# schematic.net
KiCad netlist of a schematic drawn in EAGLE
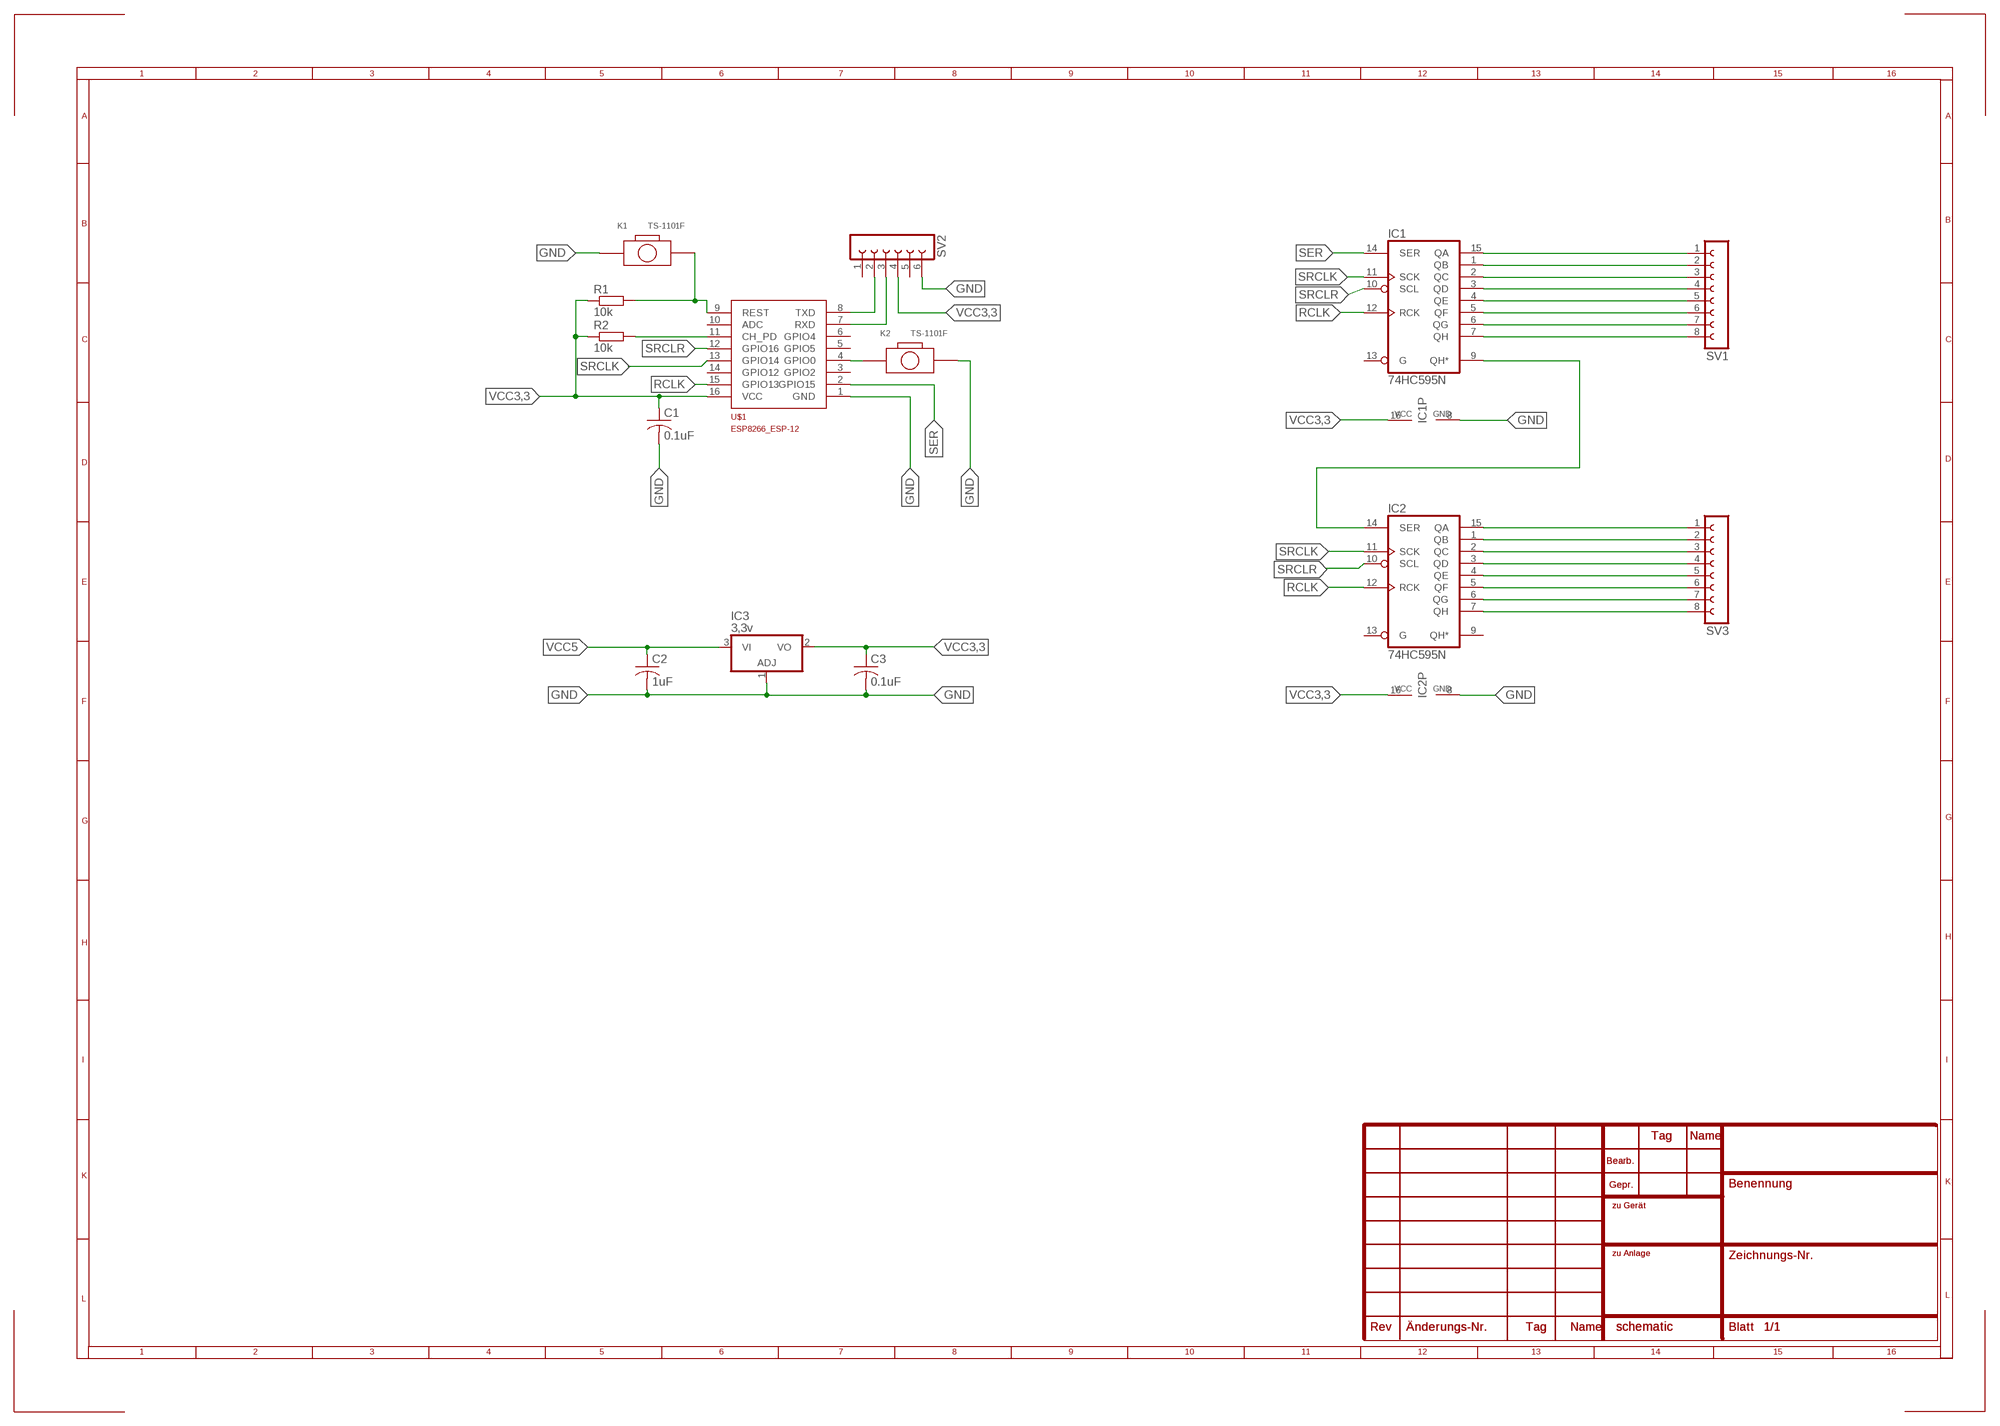
[diagram p0: schematic, sheet 1]

(export (version "E")
  (design (tool "Eeschema 10.0.6"))
  (components
    (comp (ref "C1")
      (value "0.1uF")
      (footprint "eagle-import:C1608")
      (libsource (lib "eagle-import") (part "C-USC1608"))
    )
    (comp (ref "C2")
      (value "1uF")
      (footprint "eagle-import:C1608")
      (libsource (lib "eagle-import") (part "C-USC1608"))
    )
    (comp (ref "C3")
      (value "0.1uF")
      (footprint "eagle-import:C1608")
      (libsource (lib "eagle-import") (part "C-USC1608"))
    )
    (comp (ref "IC1")
      (value "74HC595N")
      (footprint "eagle-import:DIL16")
      (libsource (lib "eagle-import") (part "74595NHC"))
    )
    (comp (ref "IC2")
      (value "74HC595N")
      (footprint "eagle-import:DIL16")
      (libsource (lib "eagle-import") (part "74595NHC"))
    )
    (comp (ref "IC3")
      (value "3,3v")
      (footprint "eagle-import:TO220H")
      (libsource (lib "eagle-import") (part "317T"))
    )
    (comp (ref "K1")
      (value "TS-1101F")
      (footprint "eagle-import:SW2-3.4X6.0X3.55MM-90D")
      (libsource (lib "eagle-import") (part "DIP-BUTTON-FRONT-WHITE(2P-3.4X6MM)"))
    )
    (comp (ref "K2")
      (value "TS-1101F")
      (footprint "eagle-import:SW2-3.4X6.0X3.55MM-90D")
      (libsource (lib "eagle-import") (part "DIP-BUTTON-FRONT-WHITE(2P-3.4X6MM)"))
    )
    (comp (ref "R1")
      (value "10k")
      (footprint "eagle-import:R0805")
      (libsource (lib "eagle-import") (part "R-EU_R0805"))
    )
    (comp (ref "R2")
      (value "10k")
      (footprint "eagle-import:R0805")
      (libsource (lib "eagle-import") (part "R-EU_R0805"))
    )
    (comp (ref "SV1")
      (value "FE08-1")
      (footprint "eagle-import:FE08")
      (libsource (lib "eagle-import") (part "FE08-1"))
    )
    (comp (ref "SV2")
      (value "FE06-1")
      (footprint "eagle-import:FE06")
      (libsource (lib "eagle-import") (part "FE06-1"))
    )
    (comp (ref "SV3")
      (value "FE08-1")
      (footprint "eagle-import:FE08")
      (libsource (lib "eagle-import") (part "FE08-1"))
    )
    (comp (ref "U$1")
      (value "ESP8266_ESP-12")
      (footprint "eagle-import:ESP8266-ESP12")
      (libsource (lib "eagle-import") (part "ESP8266_ESP-12"))
    )
  )
  (nets
    (net (code "1") (name "GND") (class "Default")
      (node (ref "C1") (pin "2") (pinfunction "2_2") (pintype "passive"))
      (node (ref "C2") (pin "2") (pinfunction "2_2") (pintype "passive"))
      (node (ref "C3") (pin "2") (pinfunction "2_2") (pintype "passive"))
      (node (ref "IC1") (pin "8") (pinfunction "GND_8") (pintype "power_in"))
      (node (ref "IC2") (pin "8") (pinfunction "GND_8") (pintype "power_in"))
      (node (ref "IC3") (pin "1") (pinfunction "ADJ_1") (pintype "input"))
      (node (ref "K1") (pin "P$1") (pinfunction "1_P$1") (pintype "bidirectional"))
      (node (ref "K2") (pin "P$2") (pinfunction "2_P$2") (pintype "bidirectional"))
      (node (ref "SV2") (pin "6") (pinfunction "6_6") (pintype "passive"))
      (node (ref "U$1") (pin "1") (pinfunction "GND_1") (pintype "bidirectional"))
    )
    (net (code "2") (name "Net-(IC1A-QA)") (class "Default")
      (node (ref "IC1") (pin "15") (pinfunction "QA_15") (pintype "tri_state"))
      (node (ref "SV1") (pin "1") (pinfunction "1_1") (pintype "passive"))
    )
    (net (code "3") (name "Net-(IC1A-QB)") (class "Default")
      (node (ref "IC1") (pin "1") (pinfunction "QB_1") (pintype "tri_state"))
      (node (ref "SV1") (pin "2") (pinfunction "2_2") (pintype "passive"))
    )
    (net (code "4") (name "Net-(IC1A-QC)") (class "Default")
      (node (ref "IC1") (pin "2") (pinfunction "QC_2") (pintype "tri_state"))
      (node (ref "SV1") (pin "3") (pinfunction "3_3") (pintype "passive"))
    )
    (net (code "5") (name "Net-(IC1A-QD)") (class "Default")
      (node (ref "IC1") (pin "3") (pinfunction "QD_3") (pintype "tri_state"))
      (node (ref "SV1") (pin "4") (pinfunction "4_4") (pintype "passive"))
    )
    (net (code "6") (name "Net-(IC1A-QE)") (class "Default")
      (node (ref "IC1") (pin "4") (pinfunction "QE_4") (pintype "tri_state"))
      (node (ref "SV1") (pin "5") (pinfunction "5_5") (pintype "passive"))
    )
    (net (code "7") (name "Net-(IC1A-QF)") (class "Default")
      (node (ref "IC1") (pin "5") (pinfunction "QF_5") (pintype "tri_state"))
      (node (ref "SV1") (pin "6") (pinfunction "6_6") (pintype "passive"))
    )
    (net (code "8") (name "Net-(IC1A-QG)") (class "Default")
      (node (ref "IC1") (pin "6") (pinfunction "QG_6") (pintype "tri_state"))
      (node (ref "SV1") (pin "7") (pinfunction "7_7") (pintype "passive"))
    )
    (net (code "9") (name "Net-(IC1A-QH)") (class "Default")
      (node (ref "IC1") (pin "7") (pinfunction "QH_7") (pintype "tri_state"))
      (node (ref "SV1") (pin "8") (pinfunction "8_8") (pintype "passive"))
    )
    (net (code "10") (name "Net-(IC1A-QH*)") (class "Default")
      (node (ref "IC1") (pin "9") (pinfunction "QH*_9") (pintype "tri_state"))
      (node (ref "IC2") (pin "14") (pinfunction "SER_14") (pintype "input"))
    )
    (net (code "11") (name "Net-(IC2A-QA)") (class "Default")
      (node (ref "IC2") (pin "15") (pinfunction "QA_15") (pintype "tri_state"))
      (node (ref "SV3") (pin "1") (pinfunction "1_1") (pintype "passive"))
    )
    (net (code "12") (name "Net-(IC2A-QB)") (class "Default")
      (node (ref "IC2") (pin "1") (pinfunction "QB_1") (pintype "tri_state"))
      (node (ref "SV3") (pin "2") (pinfunction "2_2") (pintype "passive"))
    )
    (net (code "13") (name "Net-(IC2A-QC)") (class "Default")
      (node (ref "IC2") (pin "2") (pinfunction "QC_2") (pintype "tri_state"))
      (node (ref "SV3") (pin "3") (pinfunction "3_3") (pintype "passive"))
    )
    (net (code "14") (name "Net-(IC2A-QD)") (class "Default")
      (node (ref "IC2") (pin "3") (pinfunction "QD_3") (pintype "tri_state"))
      (node (ref "SV3") (pin "4") (pinfunction "4_4") (pintype "passive"))
    )
    (net (code "15") (name "Net-(IC2A-QE)") (class "Default")
      (node (ref "IC2") (pin "4") (pinfunction "QE_4") (pintype "tri_state"))
      (node (ref "SV3") (pin "5") (pinfunction "5_5") (pintype "passive"))
    )
    (net (code "16") (name "Net-(IC2A-QF)") (class "Default")
      (node (ref "IC2") (pin "5") (pinfunction "QF_5") (pintype "tri_state"))
      (node (ref "SV3") (pin "6") (pinfunction "6_6") (pintype "passive"))
    )
    (net (code "17") (name "Net-(IC2A-QG)") (class "Default")
      (node (ref "IC2") (pin "6") (pinfunction "QG_6") (pintype "tri_state"))
      (node (ref "SV3") (pin "7") (pinfunction "7_7") (pintype "passive"))
    )
    (net (code "18") (name "Net-(IC2A-QH)") (class "Default")
      (node (ref "IC2") (pin "7") (pinfunction "QH_7") (pintype "tri_state"))
      (node (ref "SV3") (pin "8") (pinfunction "8_8") (pintype "passive"))
    )
    (net (code "19") (name "Net-(K1-2)") (class "Default")
      (node (ref "K1") (pin "P$2") (pinfunction "2_P$2") (pintype "bidirectional"))
      (node (ref "R1") (pin "2") (pinfunction "2_2") (pintype "passive"))
      (node (ref "U$1") (pin "9") (pinfunction "REST_9") (pintype "bidirectional"))
    )
    (net (code "20") (name "Net-(K2-1)") (class "Default")
      (node (ref "K2") (pin "P$1") (pinfunction "1_P$1") (pintype "bidirectional"))
      (node (ref "U$1") (pin "4") (pinfunction "GPIO0_4") (pintype "bidirectional"))
    )
    (net (code "21") (name "Net-(U$1-CH_PD)") (class "Default")
      (node (ref "R2") (pin "2") (pinfunction "2_2") (pintype "passive"))
      (node (ref "U$1") (pin "11") (pinfunction "CH_PD_11") (pintype "bidirectional"))
    )
    (net (code "22") (name "Net-(U$1-RXD)") (class "Default")
      (node (ref "SV2") (pin "3") (pinfunction "3_3") (pintype "passive"))
      (node (ref "U$1") (pin "7") (pinfunction "RXD_7") (pintype "bidirectional"))
    )
    (net (code "23") (name "Net-(U$1-TXD)") (class "Default")
      (node (ref "SV2") (pin "2") (pinfunction "2_2") (pintype "passive"))
      (node (ref "U$1") (pin "8") (pinfunction "TXD_8") (pintype "bidirectional"))
    )
    (net (code "24") (name "RCLK") (class "Default")
      (node (ref "IC1") (pin "12") (pinfunction "RCK_12") (pintype "input"))
      (node (ref "IC2") (pin "12") (pinfunction "RCK_12") (pintype "input"))
      (node (ref "U$1") (pin "15") (pinfunction "GPIO13_15") (pintype "bidirectional"))
    )
    (net (code "25") (name "SER") (class "Default")
      (node (ref "IC1") (pin "14") (pinfunction "SER_14") (pintype "input"))
      (node (ref "U$1") (pin "2") (pinfunction "GPIO15_2") (pintype "bidirectional"))
    )
    (net (code "26") (name "SRCLK") (class "Default")
      (node (ref "IC1") (pin "11") (pinfunction "SCK_11") (pintype "input"))
      (node (ref "IC2") (pin "11") (pinfunction "SCK_11") (pintype "input"))
      (node (ref "U$1") (pin "13") (pinfunction "GPIO14_13") (pintype "bidirectional"))
    )
    (net (code "27") (name "SRCLR") (class "Default")
      (node (ref "IC1") (pin "10") (pinfunction "SCL_10") (pintype "input"))
      (node (ref "IC2") (pin "10") (pinfunction "SCL_10") (pintype "input"))
      (node (ref "U$1") (pin "12") (pinfunction "GPIO16_12") (pintype "bidirectional"))
    )
    (net (code "28") (name "VCC3,3") (class "Default")
      (node (ref "C1") (pin "1") (pinfunction "1_1") (pintype "passive"))
      (node (ref "C3") (pin "1") (pinfunction "1_1") (pintype "passive"))
      (node (ref "IC1") (pin "16") (pinfunction "VCC_16") (pintype "power_in"))
      (node (ref "IC2") (pin "16") (pinfunction "VCC_16") (pintype "power_in"))
      (node (ref "IC3") (pin "2") (pinfunction "VO_2") (pintype "passive"))
      (node (ref "R1") (pin "1") (pinfunction "1_1") (pintype "passive"))
      (node (ref "R2") (pin "1") (pinfunction "1_1") (pintype "passive"))
      (node (ref "SV2") (pin "4") (pinfunction "4_4") (pintype "passive"))
      (node (ref "U$1") (pin "16") (pinfunction "VCC_16") (pintype "bidirectional"))
    )
    (net (code "29") (name "VCC5") (class "Default")
      (node (ref "C2") (pin "1") (pinfunction "1_1") (pintype "passive"))
      (node (ref "IC3") (pin "3") (pinfunction "VI_3") (pintype "input"))
    )
    (net (code "30") (name "unconnected-(IC1A-G-Pad13)") (class "Default")
      (node (ref "IC1") (pin "13") (pinfunction "G_13") (pintype "input"))
    )
    (net (code "31") (name "unconnected-(IC2A-G-Pad13)") (class "Default")
      (node (ref "IC2") (pin "13") (pinfunction "G_13") (pintype "input"))
    )
    (net (code "32") (name "unconnected-(IC2A-QH*-Pad9)") (class "Default")
      (node (ref "IC2") (pin "9") (pinfunction "QH*_9") (pintype "tri_state"))
    )
    (net (code "33") (name "unconnected-(SV2-Pad1)") (class "Default")
      (node (ref "SV2") (pin "1") (pinfunction "1_1") (pintype "passive"))
    )
    (net (code "34") (name "unconnected-(SV2-Pad5)") (class "Default")
      (node (ref "SV2") (pin "5") (pinfunction "5_5") (pintype "passive"))
    )
    (net (code "35") (name "unconnected-(U$1-ADC-Pad10)") (class "Default")
      (node (ref "U$1") (pin "10") (pinfunction "ADC_10") (pintype "bidirectional"))
    )
    (net (code "36") (name "unconnected-(U$1-GPIO2-Pad3)") (class "Default")
      (node (ref "U$1") (pin "3") (pinfunction "GPIO2_3") (pintype "bidirectional"))
    )
    (net (code "37") (name "unconnected-(U$1-GPIO4-Pad6)") (class "Default")
      (node (ref "U$1") (pin "6") (pinfunction "GPIO4_6") (pintype "bidirectional"))
    )
    (net (code "38") (name "unconnected-(U$1-GPIO5-Pad5)") (class "Default")
      (node (ref "U$1") (pin "5") (pinfunction "GPIO5_5") (pintype "bidirectional"))
    )
    (net (code "39") (name "unconnected-(U$1-GPIO12-Pad14)") (class "Default")
      (node (ref "U$1") (pin "14") (pinfunction "GPIO12_14") (pintype "bidirectional"))
    )
  )
)
